# zvs_circuit.net
KiCad netlist of a schematic drawn in Altium Designer
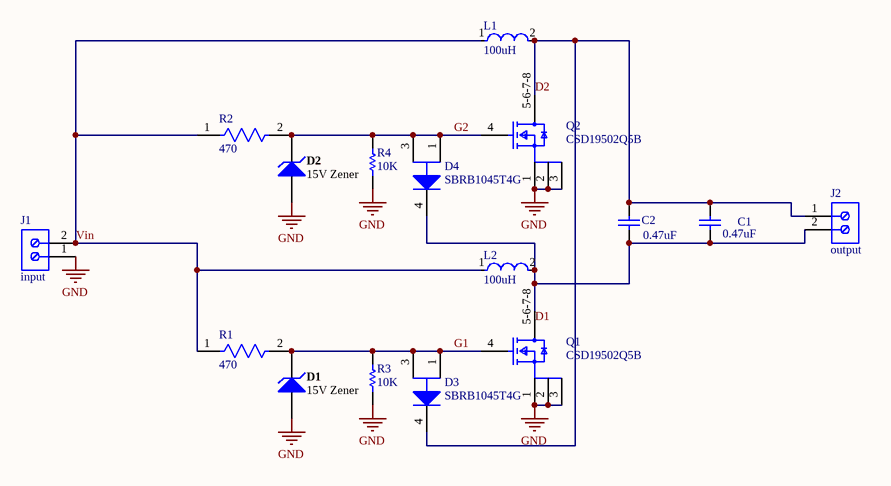
[diagram p0: zvs_circuit.SchDoc]

(export (version "E")
  (design (tool "Eeschema 10.0.6"))
  (components
    (comp (ref "C1")
      (value "0.47uF")
      (footprint "WIMA-MKS2D034701E00")
      (fields (field (name "MANUFACTURER") "Wima"))
      (libsource (lib "Altium Content Vault") (part "CAP-NP-2"))
    )
    (comp (ref "C2")
      (value "0.47uF")
      (footprint "WIMA-MKS2D034701E00")
      (fields (field (name "MANUFACTURER") "Wima"))
      (libsource (lib "Altium Content Vault") (part "CAP-NP-2"))
    )
    (comp (ref "D1")
      (value "15V Zener")
      (footprint "VISH-SOD-123-2_V")
      (description "Small Signal Zener Diode, 15 V +/- 5%, -55 to 155 degC, 2-Pin SOD-123, RoHS, Tape and Reel")
      (fields (field (name "MANUFACTURER") "Vishay Semiconductor") (field (name "TOLERANCE") "+/- 5%"))
      (libsource (lib "Altium Content Vault") (part "VISH-DZEN_A1K2-2"))
    )
    (comp (ref "D2")
      (value "15V Zener")
      (footprint "VISH-SOD-123-2_V")
      (description "Small Signal Zener Diode, 15 V +/- 5%, -55 to 155 degC, 2-Pin SOD-123, RoHS, Tape and Reel")
      (fields (field (name "MANUFACTURER") "Vishay Semiconductor") (field (name "TOLERANCE") "+/- 5%"))
      (libsource (lib "Altium Content Vault") (part "VISH-DZEN_A1K2-2"))
    )
    (comp (ref "D3")
      (value "SBRB1045T4G")
      (footprint "ONSC-D2PAK-3-418B-04_V")
      (fields (field (name "MANUFACTURER") "On Semiconductor"))
      (libsource (lib "Altium Content Vault") (part "ONSC-D-A1A3K4-3_A"))
    )
    (comp (ref "D4")
      (value "SBRB1045T4G")
      (footprint "ONSC-D2PAK-3-418B-04_V")
      (fields (field (name "MANUFACTURER") "On Semiconductor"))
      (libsource (lib "Altium Content Vault") (part "ONSC-D-A1A3K4-3_A"))
    )
    (comp (ref "J1")
      (value "input")
      (footprint "691214110002")
      (description "Serie 2141 - 3.50 mm Horizontal Entry Modular with Rising Cage Clamp WR-TBL, 2 pin")
      (fields
        (field (name "PART NUMBER") "691214110002")
        (field (name "MANUFACTURER") "Wurth Elektronik")
        (field (name "PUBLISHER") "WurthElektronik")
      )
      (libsource (lib "Altium Content Vault") (part "WE-CN-1P-F-TB2"))
    )
    (comp (ref "J2")
      (value "output")
      (footprint "691214110002")
      (description "Serie 2141 - 3.50 mm Horizontal Entry Modular with Rising Cage Clamp WR-TBL, 2 pin")
      (fields
        (field (name "PART NUMBER") "691214110002")
        (field (name "MANUFACTURER") "Wurth Elektronik")
        (field (name "PUBLISHER") "WurthElektronik")
      )
      (libsource (lib "Altium Content Vault") (part "WE-CN-1P-F-TB2"))
    )
    (comp (ref "L1")
      (value "100uH")
      (footprint "FP-PA4344_104NLT-MFG")
      (description "FIXED IND 100UH 5.3A 118 MOHM")
      (fields
        (field (name "OCTOPART") "https://octopart.com/pa4344.104nlt-pulse-65154399")
        (field (name "TOLERANCE") "20%")
      )
      (libsource (lib "Altium Content Vault") (part "725321dda6339637d4d059423bc1c3c"))
    )
    (comp (ref "L2")
      (value "100uH")
      (footprint "FP-PA4344_104NLT-MFG")
      (description "FIXED IND 100UH 5.3A 118 MOHM")
      (fields
        (field (name "OCTOPART") "https://octopart.com/pa4344.104nlt-pulse-65154399")
        (field (name "TOLERANCE") "20%")
      )
      (libsource (lib "Altium Content Vault") (part "725321dda6339637d4d059423bc1c3c"))
    )
    (comp (ref "Q1")
      (value "CSD19502Q5B")
      (footprint "FP-DNK0008A-MFG")
      (description "MOSFET N-CH 80V 100A 8SON")
      (libsource (lib "Altium Content Vault") (part "95ca5d46c4c8fe7d84c4fb5e2abfe3c"))
    )
    (comp (ref "Q2")
      (value "CSD19502Q5B")
      (footprint "FP-DNK0008A-MFG")
      (description "MOSFET N-CH 80V 100A 8SON")
      (libsource (lib "Altium Content Vault") (part "95ca5d46c4c8fe7d84c4fb5e2abfe3c"))
    )
    (comp (ref "R1")
      (value "470")
      (footprint "FP-CRCW2512-e3-IPC_B")
      (description "RES Thick Film, 470Ω, 1%, 1W, 100ppm/°C, 2512")
      (fields (field (name "TOLERANCE") "1%"))
      (libsource (lib "Altium Content Vault") (part "1029c3af85768c4190bb7ad29bc67b5"))
    )
    (comp (ref "R2")
      (value "470")
      (footprint "FP-CRCW2512-e3-IPC_B")
      (description "RES Thick Film, 470Ω, 1%, 1W, 100ppm/°C, 2512")
      (fields (field (name "TOLERANCE") "1%"))
      (libsource (lib "Altium Content Vault") (part "1029c3af85768c4190bb7ad29bc67b5"))
    )
    (comp (ref "R3")
      (value "10K")
      (footprint "RESC2013X60X35NL10T20")
      (description "Chip Resistor, 10 KOhm, +/- 1%, 0.125 W, -55 to 155 degC, 0805 (2012 Metric), RoHS, Tape and Reel")
      (fields (field (name "MANUFACTURER") "Yageo"))
      (libsource (lib "Altium Content Vault") (part "RES-2"))
    )
    (comp (ref "R4")
      (value "10K")
      (footprint "RESC2013X60X35NL10T20")
      (description "Chip Resistor, 10 KOhm, +/- 1%, 0.125 W, -55 to 155 degC, 0805 (2012 Metric), RoHS, Tape and Reel")
      (fields (field (name "MANUFACTURER") "Yageo"))
      (libsource (lib "Altium Content Vault") (part "RES-2"))
    )
  )
  (nets
    (net (code "2") (name "/D2") (class "Default")
      (node (ref "C1") (pin "2") (pinfunction "2_2") (pintype "passive"))
      (node (ref "C2") (pin "2") (pinfunction "2_2") (pintype "passive"))
      (node (ref "D3") (pin "4") (pinfunction "K_4") (pintype "passive"))
      (node (ref "J2") (pin "1") (pinfunction "1_1") (pintype "passive"))
      (node (ref "L1") (pin "2") (pinfunction "2_2") (pintype "passive"))
      (node (ref "Q2") (pin "5-6-7-8") (pinfunction "D_5-6-7-8") (pintype "passive"))
    )
    (net (code "3") (name "/G1") (class "Default")
      (node (ref "D1") (pin "2") (pinfunction "K_2") (pintype "passive"))
      (node (ref "D3") (pin "1") (pinfunction "A_1") (pintype "passive"))
      (node (ref "D3") (pin "3") (pinfunction "A_3") (pintype "passive"))
      (node (ref "Q1") (pin "4") (pinfunction "G_4") (pintype "passive"))
      (node (ref "R1") (pin "2") (pinfunction "2_2") (pintype "passive"))
      (node (ref "R3") (pin "2") (pinfunction "2_2") (pintype "passive"))
    )
    (net (code "4") (name "/G2") (class "Default")
      (node (ref "D2") (pin "2") (pinfunction "K_2") (pintype "passive"))
      (node (ref "D4") (pin "1") (pinfunction "A_1") (pintype "passive"))
      (node (ref "D4") (pin "3") (pinfunction "A_3") (pintype "passive"))
      (node (ref "Q2") (pin "4") (pinfunction "G_4") (pintype "passive"))
      (node (ref "R2") (pin "2") (pinfunction "2_2") (pintype "passive"))
      (node (ref "R4") (pin "2") (pinfunction "2_2") (pintype "passive"))
    )
    (net (code "5") (name "/Vin") (class "Default")
      (node (ref "J1") (pin "2") (pinfunction "2_2") (pintype "passive"))
      (node (ref "L1") (pin "1") (pinfunction "1_1") (pintype "passive"))
      (node (ref "L2") (pin "1") (pinfunction "1_1") (pintype "passive"))
      (node (ref "R1") (pin "1") (pinfunction "1_1") (pintype "passive"))
      (node (ref "R2") (pin "1") (pinfunction "1_1") (pintype "passive"))
    )
    (net (code "6") (name "GND") (class "Default")
      (node (ref "D1") (pin "1") (pinfunction "A_1") (pintype "passive"))
      (node (ref "D2") (pin "1") (pinfunction "A_1") (pintype "passive"))
      (node (ref "J1") (pin "1") (pinfunction "1_1") (pintype "passive"))
      (node (ref "Q1") (pin "1") (pinfunction "S_1") (pintype "passive"))
      (node (ref "Q1") (pin "2") (pinfunction "S_2") (pintype "passive"))
      (node (ref "Q1") (pin "3") (pinfunction "S_3") (pintype "passive"))
      (node (ref "Q2") (pin "1") (pinfunction "S_1") (pintype "passive"))
      (node (ref "Q2") (pin "2") (pinfunction "S_2") (pintype "passive"))
      (node (ref "Q2") (pin "3") (pinfunction "S_3") (pintype "passive"))
      (node (ref "R3") (pin "1") (pinfunction "1_1") (pintype "passive"))
      (node (ref "R4") (pin "1") (pinfunction "1_1") (pintype "passive"))
    )
    (net (code "7") (name "Net-(D4-K)") (class "Default")
      (node (ref "C1") (pin "1") (pinfunction "1_1") (pintype "passive"))
      (node (ref "C2") (pin "1") (pinfunction "1_1") (pintype "passive"))
      (node (ref "D4") (pin "4") (pinfunction "K_4") (pintype "passive"))
      (node (ref "J2") (pin "2") (pinfunction "2_2") (pintype "passive"))
      (node (ref "L2") (pin "2") (pinfunction "2_2") (pintype "passive"))
      (node (ref "Q1") (pin "5-6-7-8") (pinfunction "D_5-6-7-8") (pintype "passive"))
    )
  )
)
